# Final_Schematic.net
KiCad netlist of a schematic drawn in EAGLE
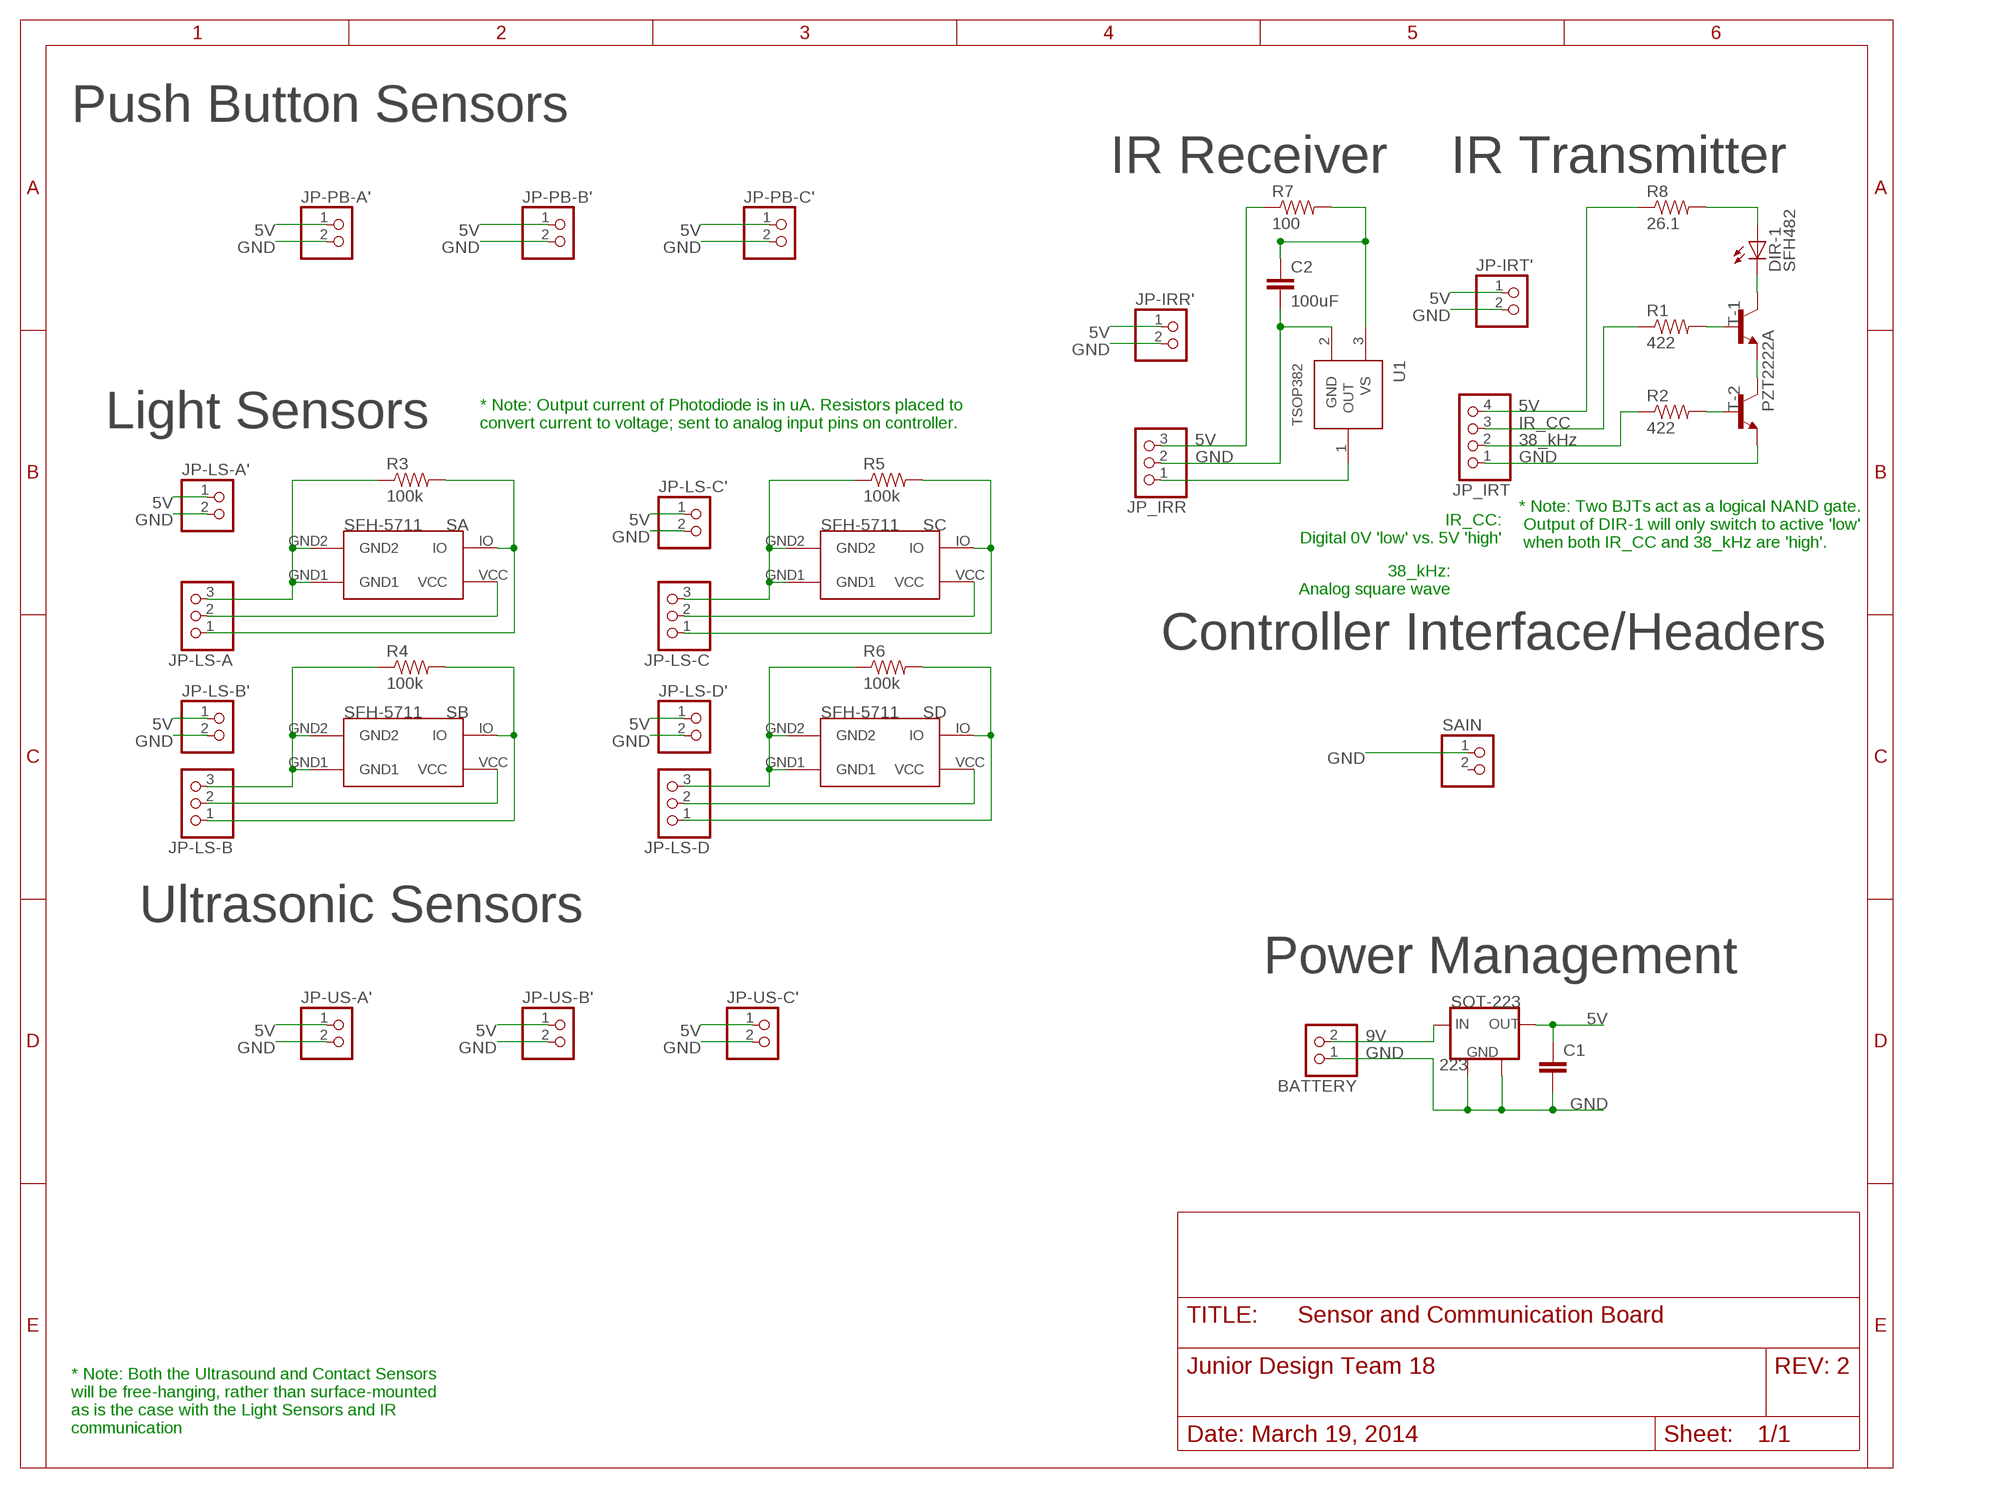
[diagram p0: schematic, sheet 1]

(export (version "E")
  (design (tool "Eeschema 10.0.6"))
  (components
    (comp (ref "BATTERY")
      (value "PINHD-1X2")
      (footprint "eagle-import:1X02")
      (libsource (lib "eagle-import") (part "PINHD-1X2"))
    )
    (comp (ref "C1")
      (value "CAP0603-CAP")
      (footprint "eagle-import:0603-CAP")
      (libsource (lib "eagle-import") (part "CAP0603-CAP"))
    )
    (comp (ref "C2")
      (value "100uF")
      (footprint "eagle-import:1206")
      (libsource (lib "eagle-import") (part "CAP1206"))
    )
    (comp (ref "DIR-1")
      (value "SFH482")
      (footprint "eagle-import:SFH482")
      (libsource (lib "eagle-import") (part "SFH482"))
    )
    (comp (ref "JP-IRR'")
      (value "PINHD-1X2")
      (footprint "eagle-import:1X02")
      (libsource (lib "eagle-import") (part "PINHD-1X2"))
    )
    (comp (ref "JP-IRT'")
      (value "PINHD-1X2")
      (footprint "eagle-import:1X02")
      (libsource (lib "eagle-import") (part "PINHD-1X2"))
    )
    (comp (ref "JP-LS-A")
      (value "PINHD-1X3")
      (footprint "eagle-import:1X03")
      (libsource (lib "eagle-import") (part "PINHD-1X3"))
    )
    (comp (ref "JP-LS-A'")
      (value "PINHD-1X2")
      (footprint "eagle-import:1X02")
      (libsource (lib "eagle-import") (part "PINHD-1X2"))
    )
    (comp (ref "JP-LS-B")
      (value "PINHD-1X3")
      (footprint "eagle-import:1X03")
      (libsource (lib "eagle-import") (part "PINHD-1X3"))
    )
    (comp (ref "JP-LS-B'")
      (value "PINHD-1X2")
      (footprint "eagle-import:1X02")
      (libsource (lib "eagle-import") (part "PINHD-1X2"))
    )
    (comp (ref "JP-LS-C")
      (value "PINHD-1X3")
      (footprint "eagle-import:1X03")
      (libsource (lib "eagle-import") (part "PINHD-1X3"))
    )
    (comp (ref "JP-LS-C'")
      (value "PINHD-1X2")
      (footprint "eagle-import:1X02")
      (libsource (lib "eagle-import") (part "PINHD-1X2"))
    )
    (comp (ref "JP-LS-D")
      (value "PINHD-1X3")
      (footprint "eagle-import:1X03")
      (libsource (lib "eagle-import") (part "PINHD-1X3"))
    )
    (comp (ref "JP-LS-D'")
      (value "PINHD-1X2")
      (footprint "eagle-import:1X02")
      (libsource (lib "eagle-import") (part "PINHD-1X2"))
    )
    (comp (ref "JP-PB-A'")
      (value "PINHD-1X2")
      (footprint "eagle-import:1X02")
      (libsource (lib "eagle-import") (part "PINHD-1X2"))
    )
    (comp (ref "JP-PB-B'")
      (value "PINHD-1X2")
      (footprint "eagle-import:1X02")
      (libsource (lib "eagle-import") (part "PINHD-1X2"))
    )
    (comp (ref "JP-PB-C'")
      (value "PINHD-1X2")
      (footprint "eagle-import:1X02")
      (libsource (lib "eagle-import") (part "PINHD-1X2"))
    )
    (comp (ref "JP-US-A'")
      (value "PINHD-1X2")
      (footprint "eagle-import:1X02")
      (libsource (lib "eagle-import") (part "PINHD-1X2"))
    )
    (comp (ref "JP-US-B'")
      (value "PINHD-1X2")
      (footprint "eagle-import:1X02")
      (libsource (lib "eagle-import") (part "PINHD-1X2"))
    )
    (comp (ref "JP-US-C'")
      (value "PINHD-1X2")
      (footprint "eagle-import:1X02")
      (libsource (lib "eagle-import") (part "PINHD-1X2"))
    )
    (comp (ref "JP_IRR")
      (value "PINHD-1X3")
      (footprint "eagle-import:1X03")
      (libsource (lib "eagle-import") (part "PINHD-1X3"))
    )
    (comp (ref "JP_IRT")
      (value "PINHD-1X4")
      (footprint "eagle-import:1X04")
      (libsource (lib "eagle-import") (part "PINHD-1X4"))
    )
    (comp (ref "R1")
      (value "422")
      (footprint "eagle-import:R2512")
      (libsource (lib "eagle-import") (part "RESISTOR2512"))
    )
    (comp (ref "R2")
      (value "422")
      (footprint "eagle-import:R2512")
      (libsource (lib "eagle-import") (part "RESISTOR2512"))
    )
    (comp (ref "R3")
      (value "100k")
      (footprint "eagle-import:0805")
      (libsource (lib "eagle-import") (part "RESISTOR0805-RES"))
    )
    (comp (ref "R4")
      (value "100k")
      (footprint "eagle-import:0805")
      (libsource (lib "eagle-import") (part "RESISTOR0805-RES"))
    )
    (comp (ref "R5")
      (value "100k")
      (footprint "eagle-import:0805")
      (libsource (lib "eagle-import") (part "RESISTOR0805-RES"))
    )
    (comp (ref "R6")
      (value "100k")
      (footprint "eagle-import:0805")
      (libsource (lib "eagle-import") (part "RESISTOR0805-RES"))
    )
    (comp (ref "R7")
      (value "100")
      (footprint "eagle-import:0805")
      (libsource (lib "eagle-import") (part "RESISTOR0805-RES"))
    )
    (comp (ref "R8")
      (value "26.1")
      (footprint "eagle-import:R2512")
      (libsource (lib "eagle-import") (part "RESISTOR2512"))
    )
    (comp (ref "SAIN")
      (value "PINHD-1X2")
      (footprint "eagle-import:1X02")
      (libsource (lib "eagle-import") (part "PINHD-1X2"))
    )
    (comp (ref "SFH-5711-A")
      (value "5711")
      (footprint "eagle-import:DIODE")
      (libsource (lib "eagle-import") (part "SFH5711"))
    )
    (comp (ref "SFH-5711-B")
      (value "5711")
      (footprint "eagle-import:DIODE")
      (libsource (lib "eagle-import") (part "SFH5711"))
    )
    (comp (ref "SFH-5711-C")
      (value "5711")
      (footprint "eagle-import:DIODE")
      (libsource (lib "eagle-import") (part "SFH5711"))
    )
    (comp (ref "SFH-5711-D")
      (value "5711")
      (footprint "eagle-import:DIODE")
      (libsource (lib "eagle-import") (part "SFH5711"))
    )
    (comp (ref "SOT-223")
      (value "223")
      (footprint "eagle-import:SOT223")
      (libsource (lib "eagle-import") (part "V_REG_LM1117SOT223"))
    )
    (comp (ref "T-1")
      (value "PZT2222A")
      (footprint "eagle-import:SOT223")
      (libsource (lib "eagle-import") (part "PZT2222A"))
    )
    (comp (ref "T-2")
      (value "PZT2222A")
      (footprint "eagle-import:SOT223")
      (libsource (lib "eagle-import") (part "PZT2222A"))
    )
    (comp (ref "U1")
      (value "TSOP382")
      (footprint "eagle-import:TSOP382")
      (libsource (lib "eagle-import") (part "TSOP382"))
    )
  )
  (nets
    (net (code "1") (name "/5V") (class "Default")
      (node (ref "C1") (pin "1") (pinfunction "1_1") (pintype "passive"))
      (node (ref "JP-IRR'") (pin "1") (pinfunction "1_1") (pintype "passive"))
      (node (ref "JP-IRT'") (pin "1") (pinfunction "1_1") (pintype "passive"))
      (node (ref "JP-LS-A'") (pin "1") (pinfunction "1_1") (pintype "passive"))
      (node (ref "JP-LS-B'") (pin "1") (pinfunction "1_1") (pintype "passive"))
      (node (ref "JP-LS-C'") (pin "1") (pinfunction "1_1") (pintype "passive"))
      (node (ref "JP-LS-D'") (pin "1") (pinfunction "1_1") (pintype "passive"))
      (node (ref "JP-PB-A'") (pin "1") (pinfunction "1_1") (pintype "passive"))
      (node (ref "JP-PB-B'") (pin "1") (pinfunction "1_1") (pintype "passive"))
      (node (ref "JP-PB-C'") (pin "1") (pinfunction "1_1") (pintype "passive"))
      (node (ref "JP-US-A'") (pin "1") (pinfunction "1_1") (pintype "passive"))
      (node (ref "JP-US-B'") (pin "1") (pinfunction "1_1") (pintype "passive"))
      (node (ref "JP-US-C'") (pin "1") (pinfunction "1_1") (pintype "passive"))
      (node (ref "SOT-223") (pin "GND1") (pinfunction "OUT_GND1") (pintype "output"))
    )
    (net (code "2") (name "/GND") (class "Default")
      (node (ref "BATTERY") (pin "1") (pinfunction "1_1") (pintype "passive"))
      (node (ref "C1") (pin "2") (pinfunction "2_2") (pintype "passive"))
      (node (ref "JP-IRR'") (pin "2") (pinfunction "2_2") (pintype "passive"))
      (node (ref "JP-IRT'") (pin "2") (pinfunction "2_2") (pintype "passive"))
      (node (ref "JP-LS-A'") (pin "2") (pinfunction "2_2") (pintype "passive"))
      (node (ref "JP-LS-B'") (pin "2") (pinfunction "2_2") (pintype "passive"))
      (node (ref "JP-LS-C'") (pin "2") (pinfunction "2_2") (pintype "passive"))
      (node (ref "JP-LS-D'") (pin "2") (pinfunction "2_2") (pintype "passive"))
      (node (ref "JP-PB-A'") (pin "2") (pinfunction "2_2") (pintype "passive"))
      (node (ref "JP-PB-B'") (pin "2") (pinfunction "2_2") (pintype "passive"))
      (node (ref "JP-PB-C'") (pin "2") (pinfunction "2_2") (pintype "passive"))
      (node (ref "JP-US-A'") (pin "2") (pinfunction "2_2") (pintype "passive"))
      (node (ref "JP-US-B'") (pin "2") (pinfunction "2_2") (pintype "passive"))
      (node (ref "JP-US-C'") (pin "2") (pinfunction "2_2") (pintype "passive"))
      (node (ref "SAIN") (pin "1") (pinfunction "1_1") (pintype "passive"))
      (node (ref "SOT-223") (pin "GND2") (pinfunction "GND1_GND2") (pintype "output"))
      (node (ref "SOT-223") (pin "IN") (pinfunction "GND2_IN") (pintype "input"))
    )
    (net (code "3") (name "Net-(DIR-1-C)") (class "Default")
      (node (ref "DIR-1") (pin "K") (pinfunction "C_K") (pintype "passive"))
      (node (ref "T-1") (pin "2") (pinfunction "C_2") (pintype "passive"))
      (node (ref "T-1") (pin "4") (pinfunction "C_4") (pintype "passive"))
    )
    (net (code "4") (name "Net-(DIR-1-PadA)") (class "Default")
      (node (ref "DIR-1") (pin "A") (pinfunction "A_A") (pintype "passive"))
      (node (ref "R8") (pin "2") (pinfunction "2_2") (pintype "passive"))
    )
    (net (code "5") (name "Net-(JP-LS-A-Pad1)") (class "Default")
      (node (ref "JP-LS-A") (pin "1") (pinfunction "1_1") (pintype "passive"))
      (node (ref "R3") (pin "2") (pinfunction "2_2") (pintype "passive"))
      (node (ref "SFH-5711-A") (pin "IO") (pinfunction "IO_IO") (pintype "bidirectional"))
    )
    (net (code "6") (name "Net-(JP-LS-A-Pad2)") (class "Default")
      (node (ref "JP-LS-A") (pin "2") (pinfunction "2_2") (pintype "passive"))
      (node (ref "SFH-5711-A") (pin "VCC") (pinfunction "VCC_VCC") (pintype "bidirectional"))
    )
    (net (code "7") (name "Net-(JP-LS-A-Pad3)") (class "Default")
      (node (ref "JP-LS-A") (pin "3") (pinfunction "3_3") (pintype "passive"))
      (node (ref "R3") (pin "1") (pinfunction "1_1") (pintype "passive"))
      (node (ref "SFH-5711-A") (pin "GND1") (pinfunction "GND1_GND1") (pintype "bidirectional"))
      (node (ref "SFH-5711-A") (pin "GND2") (pinfunction "GND2_GND2") (pintype "bidirectional"))
    )
    (net (code "8") (name "Net-(JP-LS-B-Pad1)") (class "Default")
      (node (ref "JP-LS-B") (pin "1") (pinfunction "1_1") (pintype "passive"))
      (node (ref "R4") (pin "2") (pinfunction "2_2") (pintype "passive"))
      (node (ref "SFH-5711-B") (pin "IO") (pinfunction "IO_IO") (pintype "bidirectional"))
    )
    (net (code "9") (name "Net-(JP-LS-B-Pad2)") (class "Default")
      (node (ref "JP-LS-B") (pin "2") (pinfunction "2_2") (pintype "passive"))
      (node (ref "SFH-5711-B") (pin "VCC") (pinfunction "VCC_VCC") (pintype "bidirectional"))
    )
    (net (code "10") (name "Net-(JP-LS-B-Pad3)") (class "Default")
      (node (ref "JP-LS-B") (pin "3") (pinfunction "3_3") (pintype "passive"))
      (node (ref "R4") (pin "1") (pinfunction "1_1") (pintype "passive"))
      (node (ref "SFH-5711-B") (pin "GND1") (pinfunction "GND1_GND1") (pintype "bidirectional"))
      (node (ref "SFH-5711-B") (pin "GND2") (pinfunction "GND2_GND2") (pintype "bidirectional"))
    )
    (net (code "11") (name "Net-(JP-LS-C-Pad1)") (class "Default")
      (node (ref "JP-LS-C") (pin "1") (pinfunction "1_1") (pintype "passive"))
      (node (ref "R5") (pin "2") (pinfunction "2_2") (pintype "passive"))
      (node (ref "SFH-5711-C") (pin "IO") (pinfunction "IO_IO") (pintype "bidirectional"))
    )
    (net (code "12") (name "Net-(JP-LS-C-Pad2)") (class "Default")
      (node (ref "JP-LS-C") (pin "2") (pinfunction "2_2") (pintype "passive"))
      (node (ref "SFH-5711-C") (pin "VCC") (pinfunction "VCC_VCC") (pintype "bidirectional"))
    )
    (net (code "13") (name "Net-(JP-LS-C-Pad3)") (class "Default")
      (node (ref "JP-LS-C") (pin "3") (pinfunction "3_3") (pintype "passive"))
      (node (ref "R5") (pin "1") (pinfunction "1_1") (pintype "passive"))
      (node (ref "SFH-5711-C") (pin "GND1") (pinfunction "GND1_GND1") (pintype "bidirectional"))
      (node (ref "SFH-5711-C") (pin "GND2") (pinfunction "GND2_GND2") (pintype "bidirectional"))
    )
    (net (code "14") (name "Net-(JP-LS-D-Pad1)") (class "Default")
      (node (ref "JP-LS-D") (pin "1") (pinfunction "1_1") (pintype "passive"))
      (node (ref "R6") (pin "2") (pinfunction "2_2") (pintype "passive"))
      (node (ref "SFH-5711-D") (pin "IO") (pinfunction "IO_IO") (pintype "bidirectional"))
    )
    (net (code "15") (name "Net-(JP-LS-D-Pad2)") (class "Default")
      (node (ref "JP-LS-D") (pin "2") (pinfunction "2_2") (pintype "passive"))
      (node (ref "SFH-5711-D") (pin "VCC") (pinfunction "VCC_VCC") (pintype "bidirectional"))
    )
    (net (code "16") (name "Net-(JP-LS-D-Pad3)") (class "Default")
      (node (ref "JP-LS-D") (pin "3") (pinfunction "3_3") (pintype "passive"))
      (node (ref "R6") (pin "1") (pinfunction "1_1") (pintype "passive"))
      (node (ref "SFH-5711-D") (pin "GND1") (pinfunction "GND1_GND1") (pintype "bidirectional"))
      (node (ref "SFH-5711-D") (pin "GND2") (pinfunction "GND2_GND2") (pintype "bidirectional"))
    )
    (net (code "17") (name "Net-(JP_IRR-Pad3)") (class "Default")
      (node (ref "JP_IRR") (pin "3") (pinfunction "3_3") (pintype "passive"))
      (node (ref "R7") (pin "1") (pinfunction "1_1") (pintype "passive"))
    )
    (net (code "18") (name "Net-(JP_IRT-Pad2)") (class "Default")
      (node (ref "JP_IRT") (pin "2") (pinfunction "2_2") (pintype "passive"))
      (node (ref "R2") (pin "1") (pinfunction "1_1") (pintype "passive"))
    )
    (net (code "19") (name "Net-(JP_IRT-Pad3)") (class "Default")
      (node (ref "JP_IRT") (pin "3") (pinfunction "3_3") (pintype "passive"))
      (node (ref "R1") (pin "1") (pinfunction "1_1") (pintype "passive"))
    )
    (net (code "20") (name "Net-(JP_IRT-Pad4)") (class "Default")
      (node (ref "JP_IRT") (pin "4") (pinfunction "4_4") (pintype "passive"))
      (node (ref "R8") (pin "1") (pinfunction "1_1") (pintype "passive"))
    )
    (net (code "21") (name "Net-(SOT-223-IN)") (class "Default")
      (node (ref "BATTERY") (pin "2") (pinfunction "2_2") (pintype "passive"))
      (node (ref "SOT-223") (pin "OUT") (pinfunction "IN_OUT") (pintype "input"))
    )
    (net (code "22") (name "Net-(T-1-B)") (class "Default")
      (node (ref "R1") (pin "2") (pinfunction "2_2") (pintype "passive"))
      (node (ref "T-1") (pin "1") (pinfunction "B_1") (pintype "passive"))
    )
    (net (code "23") (name "Net-(T-1-E)") (class "Default")
      (node (ref "T-1") (pin "3") (pinfunction "E_3") (pintype "passive"))
      (node (ref "T-2") (pin "2") (pinfunction "C_2") (pintype "passive"))
      (node (ref "T-2") (pin "4") (pinfunction "C_4") (pintype "passive"))
    )
    (net (code "24") (name "Net-(T-2-B)") (class "Default")
      (node (ref "R2") (pin "2") (pinfunction "2_2") (pintype "passive"))
      (node (ref "T-2") (pin "1") (pinfunction "B_1") (pintype "passive"))
    )
    (net (code "25") (name "Net-(T-2-E)") (class "Default")
      (node (ref "JP_IRT") (pin "1") (pinfunction "1_1") (pintype "passive"))
      (node (ref "T-2") (pin "3") (pinfunction "E_3") (pintype "passive"))
    )
    (net (code "26") (name "Net-(U1-GND)") (class "Default")
      (node (ref "C2") (pin "2") (pinfunction "2_2") (pintype "passive"))
      (node (ref "JP_IRR") (pin "2") (pinfunction "2_2") (pintype "passive"))
      (node (ref "U1") (pin "2") (pinfunction "GND_2") (pintype "bidirectional"))
    )
    (net (code "27") (name "Net-(U1-OUT)") (class "Default")
      (node (ref "JP_IRR") (pin "1") (pinfunction "1_1") (pintype "passive"))
      (node (ref "U1") (pin "1") (pinfunction "OUT_1") (pintype "bidirectional"))
    )
    (net (code "28") (name "Net-(U1-VS)") (class "Default")
      (node (ref "C2") (pin "1") (pinfunction "1_1") (pintype "passive"))
      (node (ref "R7") (pin "2") (pinfunction "2_2") (pintype "passive"))
      (node (ref "U1") (pin "3") (pinfunction "VS_3") (pintype "bidirectional"))
    )
    (net (code "29") (name "unconnected-(SAIN-Pad2)") (class "Default")
      (node (ref "SAIN") (pin "2") (pinfunction "2_2") (pintype "passive"))
    )
  )
)
